# W5500.net
KiCad netlist of a schematic drawn in Altium Designer
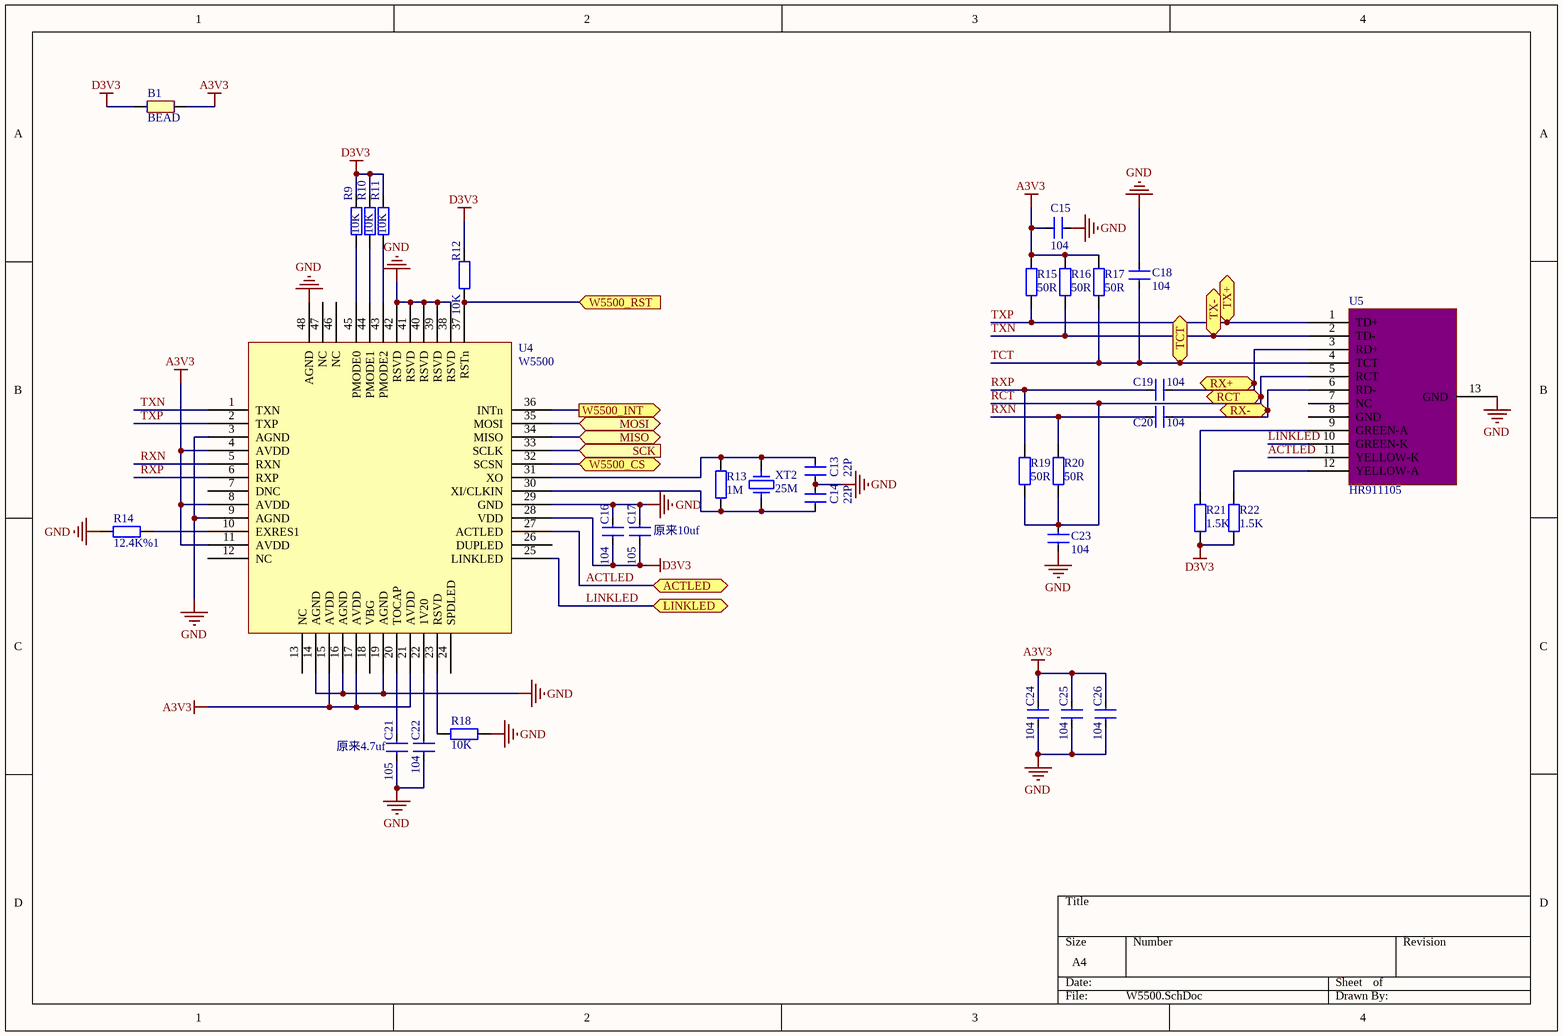
[diagram p0: W5500.SchDoc]

(export (version "E")
  (design (tool "Eeschema 10.0.6"))
  (components
    (comp (ref "B1")
      (value "BEAD")
      (footprint "0603L")
      (description "磁珠")
      (libsource (lib "lib_AD") (part "BEAD"))
    )
    (comp (ref "C13")
      (value "22P")
      (footprint "0603C")
      (description "普通小电容")
      (libsource (lib "lib_AD") (part "CAP"))
    )
    (comp (ref "C14")
      (value "22P")
      (footprint "0603C")
      (description "普通小电容")
      (libsource (lib "lib_AD") (part "CAP"))
    )
    (comp (ref "C15")
      (value "104")
      (footprint "0603C")
      (description "普通小电容")
      (libsource (lib "lib_AD") (part "CAP"))
    )
    (comp (ref "C16")
      (value "104")
      (footprint "0603C")
      (description "普通小电容")
      (libsource (lib "lib_AD") (part "CAP"))
    )
    (comp (ref "C17")
      (value "105")
      (footprint "0603C")
      (description "普通小电容")
      (libsource (lib "lib_AD") (part "CAP"))
    )
    (comp (ref "C18")
      (value "104")
      (footprint "0603C")
      (description "普通小电容")
      (libsource (lib "lib_AD") (part "CAP"))
    )
    (comp (ref "C19")
      (value "104")
      (footprint "0603C")
      (description "普通小电容")
      (libsource (lib "lib_AD") (part "CAP"))
    )
    (comp (ref "C20")
      (value "104")
      (footprint "0603C")
      (description "普通小电容")
      (libsource (lib "lib_AD") (part "CAP"))
    )
    (comp (ref "C21")
      (value "105")
      (footprint "0603C")
      (description "普通小电容")
      (libsource (lib "lib_AD") (part "CAP"))
    )
    (comp (ref "C22")
      (value "104")
      (footprint "0603C")
      (description "普通小电容")
      (libsource (lib "lib_AD") (part "CAP"))
    )
    (comp (ref "C23")
      (value "104")
      (footprint "0603C")
      (description "普通小电容")
      (libsource (lib "lib_AD") (part "CAP"))
    )
    (comp (ref "C24")
      (value "104")
      (footprint "0603C")
      (description "普通小电容")
      (libsource (lib "lib_AD") (part "CAP"))
    )
    (comp (ref "C25")
      (value "104")
      (footprint "0603C")
      (description "普通小电容")
      (libsource (lib "lib_AD") (part "CAP"))
    )
    (comp (ref "C26")
      (value "104")
      (footprint "0603C")
      (description "普通小电容")
      (libsource (lib "lib_AD") (part "CAP"))
    )
    (comp (ref "R9")
      (value "10K")
      (footprint "0603R")
      (description "普通电阻")
      (libsource (lib "lib_AD") (part "RES"))
    )
    (comp (ref "R10")
      (value "10K")
      (footprint "0603R")
      (description "普通电阻")
      (libsource (lib "lib_AD") (part "RES"))
    )
    (comp (ref "R11")
      (value "10K")
      (footprint "0603R")
      (description "普通电阻")
      (libsource (lib "lib_AD") (part "RES"))
    )
    (comp (ref "R12")
      (value "10K")
      (footprint "0603R")
      (description "普通电阻")
      (libsource (lib "lib_AD") (part "RES"))
    )
    (comp (ref "R13")
      (value "1M")
      (footprint "0603R")
      (description "普通电阻")
      (libsource (lib "lib_AD") (part "RES"))
    )
    (comp (ref "R14")
      (value "12.4K%1")
      (footprint "0603R")
      (description "普通电阻")
      (libsource (lib "") (part "RES_2"))
    )
    (comp (ref "R15")
      (value "50R")
      (footprint "0603R")
      (description "普通电阻")
      (libsource (lib "lib_AD") (part "RES"))
    )
    (comp (ref "R16")
      (value "50R")
      (footprint "0603R")
      (description "普通电阻")
      (libsource (lib "lib_AD") (part "RES"))
    )
    (comp (ref "R17")
      (value "50R")
      (footprint "0603R")
      (description "普通电阻")
      (libsource (lib "lib_AD") (part "RES"))
    )
    (comp (ref "R18")
      (value "10K")
      (footprint "0603R")
      (description "普通电阻")
      (libsource (lib "") (part "RES_2"))
    )
    (comp (ref "R19")
      (value "50R")
      (footprint "0603R")
      (description "普通电阻")
      (libsource (lib "") (part "RES_1"))
    )
    (comp (ref "R20")
      (value "50R")
      (footprint "0603R")
      (description "普通电阻")
      (libsource (lib "") (part "RES_1"))
    )
    (comp (ref "R21")
      (value "1.5K")
      (footprint "0603R")
      (description "普通电阻")
      (libsource (lib "lib_AD") (part "RES"))
    )
    (comp (ref "R22")
      (value "1.5K")
      (footprint "0603R")
      (description "普通电阻")
      (libsource (lib "lib_AD") (part "RES"))
    )
    (comp (ref "U4") (value "W5500") (footprint "LQFP48") (libsource (lib "IC") (part "W5500")))
    (comp (ref "U5")
      (value "HR911105")
      (footprint "HR911105A")
      (libsource (lib "Connectors") (part "HR911105"))
    )
    (comp (ref "XT2")
      (value "25M")
      (footprint "5032")
      (description "晶振")
      (libsource (lib "lib_AD") (part "XT"))
    )
  )
  (nets
    (net (code "1") (name "/ACTLED") (class "Default")
      (node (ref "U4") (pin "27") (pinfunction "ACTLED_27") (pintype "passive"))
      (node (ref "U5") (pin "11") (pinfunction "YELLOW-K_11") (pintype "power_in"))
    )
    (net (code "2") (name "/LINKLED") (class "Default")
      (node (ref "U4") (pin "25") (pinfunction "LINKLED_25") (pintype "passive"))
      (node (ref "U5") (pin "10") (pinfunction "GREEN-K_10") (pintype "power_in"))
    )
    (net (code "3") (name "/MISO") (class "Default")
      (node (ref "U4") (pin "34") (pinfunction "MISO_34") (pintype "passive"))
    )
    (net (code "4") (name "/MOSI") (class "Default")
      (node (ref "U4") (pin "35") (pinfunction "MOSI_35") (pintype "passive"))
    )
    (net (code "5") (name "/RCT") (class "Default")
      (node (ref "C23") (pin "1") (pinfunction "1_1") (pintype "passive"))
      (node (ref "R19") (pin "2") (pinfunction "2_2") (pintype "passive"))
      (node (ref "R20") (pin "2") (pinfunction "2_2") (pintype "passive"))
      (node (ref "U5") (pin "5") (pinfunction "RCT_5") (pintype "power_in"))
    )
    (net (code "6") (name "/RX+") (class "Default")
      (node (ref "C19") (pin "1") (pinfunction "1_1") (pintype "passive"))
      (node (ref "U5") (pin "3") (pinfunction "RD+_3") (pintype "power_in"))
    )
    (net (code "7") (name "/RX-") (class "Default")
      (node (ref "C20") (pin "1") (pinfunction "1_1") (pintype "passive"))
      (node (ref "U5") (pin "6") (pinfunction "RD-_6") (pintype "power_in"))
    )
    (net (code "8") (name "/RXN") (class "Default")
      (node (ref "C20") (pin "2") (pinfunction "2_2") (pintype "passive"))
      (node (ref "R20") (pin "1") (pinfunction "1_1") (pintype "passive"))
      (node (ref "U4") (pin "5") (pinfunction "RXN_5") (pintype "passive"))
    )
    (net (code "9") (name "/RXP") (class "Default")
      (node (ref "C19") (pin "2") (pinfunction "2_2") (pintype "passive"))
      (node (ref "R19") (pin "1") (pinfunction "1_1") (pintype "passive"))
      (node (ref "U4") (pin "6") (pinfunction "RXP_6") (pintype "passive"))
    )
    (net (code "10") (name "/SCK") (class "Default")
      (node (ref "U4") (pin "33") (pinfunction "SCLK_33") (pintype "passive"))
    )
    (net (code "11") (name "/TCT") (class "Default")
      (node (ref "C18") (pin "2") (pinfunction "2_2") (pintype "passive"))
      (node (ref "R17") (pin "1") (pinfunction "1_1") (pintype "passive"))
      (node (ref "U5") (pin "4") (pinfunction "TCT_4") (pintype "power_in"))
    )
    (net (code "12") (name "/TXN") (class "Default")
      (node (ref "R16") (pin "1") (pinfunction "1_1") (pintype "passive"))
      (node (ref "U4") (pin "1") (pinfunction "TXN_1") (pintype "passive"))
      (node (ref "U5") (pin "2") (pinfunction "TD-_2") (pintype "power_in"))
    )
    (net (code "13") (name "/TXP") (class "Default")
      (node (ref "R15") (pin "1") (pinfunction "1_1") (pintype "passive"))
      (node (ref "U4") (pin "2") (pinfunction "TXP_2") (pintype "passive"))
      (node (ref "U5") (pin "1") (pinfunction "TD+_1") (pintype "power_in"))
    )
    (net (code "14") (name "/W5500_CS") (class "Default")
      (node (ref "U4") (pin "32") (pinfunction "SCSN_32") (pintype "passive"))
    )
    (net (code "15") (name "/W5500_INT") (class "Default")
      (node (ref "U4") (pin "36") (pinfunction "INTn_36") (pintype "passive"))
    )
    (net (code "16") (name "/W5500_RST") (class "Default")
      (node (ref "R12") (pin "1") (pinfunction "1_1") (pintype "passive"))
      (node (ref "U4") (pin "37") (pinfunction "RSTn_37") (pintype "passive"))
    )
    (net (code "17") (name "A3V3") (class "Default")
      (node (ref "B1") (pin "2") (pinfunction "2_2") (pintype "passive"))
      (node (ref "C15") (pin "1") (pinfunction "1_1") (pintype "passive"))
      (node (ref "C24") (pin "2") (pinfunction "2_2") (pintype "passive"))
      (node (ref "C25") (pin "2") (pinfunction "2_2") (pintype "passive"))
      (node (ref "C26") (pin "2") (pinfunction "2_2") (pintype "passive"))
      (node (ref "R15") (pin "2") (pinfunction "2_2") (pintype "passive"))
      (node (ref "R16") (pin "2") (pinfunction "2_2") (pintype "passive"))
      (node (ref "R17") (pin "2") (pinfunction "2_2") (pintype "passive"))
      (node (ref "U4") (pin "11") (pinfunction "AVDD_11") (pintype "passive"))
      (node (ref "U4") (pin "15") (pinfunction "AVDD_15") (pintype "passive"))
      (node (ref "U4") (pin "17") (pinfunction "AVDD_17") (pintype "passive"))
      (node (ref "U4") (pin "21") (pinfunction "AVDD_21") (pintype "passive"))
      (node (ref "U4") (pin "4") (pinfunction "AVDD_4") (pintype "passive"))
      (node (ref "U4") (pin "8") (pinfunction "AVDD_8") (pintype "passive"))
    )
    (net (code "18") (name "D3V3") (class "Default")
      (node (ref "B1") (pin "1") (pinfunction "1_1") (pintype "passive"))
      (node (ref "C16") (pin "1") (pinfunction "1_1") (pintype "passive"))
      (node (ref "C17") (pin "1") (pinfunction "1_1") (pintype "passive"))
      (node (ref "R10") (pin "2") (pinfunction "2_2") (pintype "passive"))
      (node (ref "R11") (pin "2") (pinfunction "2_2") (pintype "passive"))
      (node (ref "R12") (pin "2") (pinfunction "2_2") (pintype "passive"))
      (node (ref "R21") (pin "1") (pinfunction "1_1") (pintype "passive"))
      (node (ref "R22") (pin "1") (pinfunction "1_1") (pintype "passive"))
      (node (ref "R9") (pin "2") (pinfunction "2_2") (pintype "passive"))
      (node (ref "U4") (pin "28") (pinfunction "VDD_28") (pintype "passive"))
    )
    (net (code "19") (name "GND") (class "Default")
      (node (ref "C13") (pin "1") (pinfunction "1_1") (pintype "passive"))
      (node (ref "C14") (pin "2") (pinfunction "2_2") (pintype "passive"))
      (node (ref "C15") (pin "2") (pinfunction "2_2") (pintype "passive"))
      (node (ref "C16") (pin "2") (pinfunction "2_2") (pintype "passive"))
      (node (ref "C17") (pin "2") (pinfunction "2_2") (pintype "passive"))
      (node (ref "C18") (pin "1") (pinfunction "1_1") (pintype "passive"))
      (node (ref "C21") (pin "1") (pinfunction "1_1") (pintype "passive"))
      (node (ref "C22") (pin "1") (pinfunction "1_1") (pintype "passive"))
      (node (ref "C23") (pin "2") (pinfunction "2_2") (pintype "passive"))
      (node (ref "C24") (pin "1") (pinfunction "1_1") (pintype "passive"))
      (node (ref "C25") (pin "1") (pinfunction "1_1") (pintype "passive"))
      (node (ref "C26") (pin "1") (pinfunction "1_1") (pintype "passive"))
      (node (ref "R14") (pin "2") (pinfunction "2_2") (pintype "passive"))
      (node (ref "R18") (pin "1") (pinfunction "1_1") (pintype "passive"))
      (node (ref "U4") (pin "14") (pinfunction "AGND_14") (pintype "passive"))
      (node (ref "U4") (pin "16") (pinfunction "AGND_16") (pintype "passive"))
      (node (ref "U4") (pin "19") (pinfunction "AGND_19") (pintype "passive"))
      (node (ref "U4") (pin "29") (pinfunction "GND_29") (pintype "passive"))
      (node (ref "U4") (pin "3") (pinfunction "AGND_3") (pintype "passive"))
      (node (ref "U4") (pin "38") (pinfunction "RSVD_38") (pintype "passive"))
      (node (ref "U4") (pin "39") (pinfunction "RSVD_39") (pintype "passive"))
      (node (ref "U4") (pin "40") (pinfunction "RSVD_40") (pintype "passive"))
      (node (ref "U4") (pin "41") (pinfunction "RSVD_41") (pintype "passive"))
      (node (ref "U4") (pin "42") (pinfunction "RSVD_42") (pintype "passive"))
      (node (ref "U4") (pin "48") (pinfunction "AGND_48") (pintype "passive"))
      (node (ref "U4") (pin "9") (pinfunction "AGND_9") (pintype "passive"))
      (node (ref "U5") (pin "13") (pinfunction "GND_13") (pintype "passive"))
    )
    (net (code "20") (name "Net-(R18-Pad2)") (class "Default")
      (node (ref "R18") (pin "2") (pinfunction "2_2") (pintype "passive"))
      (node (ref "U4") (pin "23") (pinfunction "RSVD_23") (pintype "passive"))
    )
    (net (code "21") (name "Net-(U4-1V20)") (class "Default")
      (node (ref "C22") (pin "2") (pinfunction "2_2") (pintype "passive"))
      (node (ref "U4") (pin "22") (pinfunction "1V20_22") (pintype "passive"))
    )
    (net (code "22") (name "Net-(U4-EXRES1)") (class "Default")
      (node (ref "R14") (pin "1") (pinfunction "1_1") (pintype "passive"))
      (node (ref "U4") (pin "10") (pinfunction "EXRES1_10") (pintype "passive"))
    )
    (net (code "23") (name "Net-(U4-PMODE0)") (class "Default")
      (node (ref "R9") (pin "1") (pinfunction "1_1") (pintype "passive"))
      (node (ref "U4") (pin "45") (pinfunction "PMODE0_45") (pintype "passive"))
    )
    (net (code "24") (name "Net-(U4-PMODE1)") (class "Default")
      (node (ref "R10") (pin "1") (pinfunction "1_1") (pintype "passive"))
      (node (ref "U4") (pin "44") (pinfunction "PMODE1_44") (pintype "passive"))
    )
    (net (code "25") (name "Net-(U4-PMODE2)") (class "Default")
      (node (ref "R11") (pin "1") (pinfunction "1_1") (pintype "passive"))
      (node (ref "U4") (pin "43") (pinfunction "PMODE2_43") (pintype "passive"))
    )
    (net (code "26") (name "Net-(U4-TOCAP)") (class "Default")
      (node (ref "C21") (pin "2") (pinfunction "2_2") (pintype "passive"))
      (node (ref "U4") (pin "20") (pinfunction "TOCAP_20") (pintype "passive"))
    )
    (net (code "27") (name "Net-(U4-XI{slash}CLKIN)") (class "Default")
      (node (ref "C14") (pin "1") (pinfunction "1_1") (pintype "passive"))
      (node (ref "R13") (pin "1") (pinfunction "1_1") (pintype "passive"))
      (node (ref "U4") (pin "30") (pinfunction "XI/CLKIN_30") (pintype "passive"))
      (node (ref "XT2") (pin "1") (pinfunction "1_1") (pintype "passive"))
    )
    (net (code "28") (name "Net-(U4-XO)") (class "Default")
      (node (ref "C13") (pin "2") (pinfunction "2_2") (pintype "passive"))
      (node (ref "R13") (pin "2") (pinfunction "2_2") (pintype "passive"))
      (node (ref "U4") (pin "31") (pinfunction "XO_31") (pintype "passive"))
      (node (ref "XT2") (pin "2") (pinfunction "2_2") (pintype "passive"))
    )
    (net (code "29") (name "Net-(U5-GREEN-A)") (class "Default")
      (node (ref "R21") (pin "2") (pinfunction "2_2") (pintype "passive"))
      (node (ref "U5") (pin "9") (pinfunction "GREEN-A_9") (pintype "power_in"))
    )
    (net (code "30") (name "Net-(U5-YELLOW-A)") (class "Default")
      (node (ref "R22") (pin "2") (pinfunction "2_2") (pintype "passive"))
      (node (ref "U5") (pin "12") (pinfunction "YELLOW-A_12") (pintype "power_in"))
    )
    (net (code "31") (name "unconnected-(U4-DNC-Pad7)") (class "Default")
      (node (ref "U4") (pin "7") (pinfunction "DNC_7") (pintype "passive"))
    )
    (net (code "32") (name "unconnected-(U4-DUPLED-Pad26)") (class "Default")
      (node (ref "U4") (pin "26") (pinfunction "DUPLED_26") (pintype "passive"))
    )
    (net (code "33") (name "unconnected-(U4-NC-Pad12)") (class "Default")
      (node (ref "U4") (pin "12") (pinfunction "NC_12") (pintype "passive"))
    )
    (net (code "34") (name "unconnected-(U4-NC-Pad13)") (class "Default")
      (node (ref "U4") (pin "13") (pinfunction "NC_13") (pintype "passive"))
    )
    (net (code "35") (name "unconnected-(U4-NC-Pad46)") (class "Default")
      (node (ref "U4") (pin "46") (pinfunction "NC_46") (pintype "passive"))
    )
    (net (code "36") (name "unconnected-(U4-NC-Pad47)") (class "Default")
      (node (ref "U4") (pin "47") (pinfunction "NC_47") (pintype "passive"))
    )
    (net (code "37") (name "unconnected-(U4-SPDLED-Pad24)") (class "Default")
      (node (ref "U4") (pin "24") (pinfunction "SPDLED_24") (pintype "passive"))
    )
    (net (code "38") (name "unconnected-(U4-VBG-Pad18)") (class "Default")
      (node (ref "U4") (pin "18") (pinfunction "VBG_18") (pintype "passive"))
    )
    (net (code "39") (name "unconnected-(U5-GND-Pad8)") (class "Default")
      (node (ref "U5") (pin "8") (pinfunction "GND_8") (pintype "power_in"))
    )
    (net (code "40") (name "unconnected-(U5-NC-Pad7)") (class "Default")
      (node (ref "U5") (pin "7") (pinfunction "NC_7") (pintype "power_in"))
    )
  )
)
